# pcf.net
KiCad netlist of a schematic drawn in Altium Designer
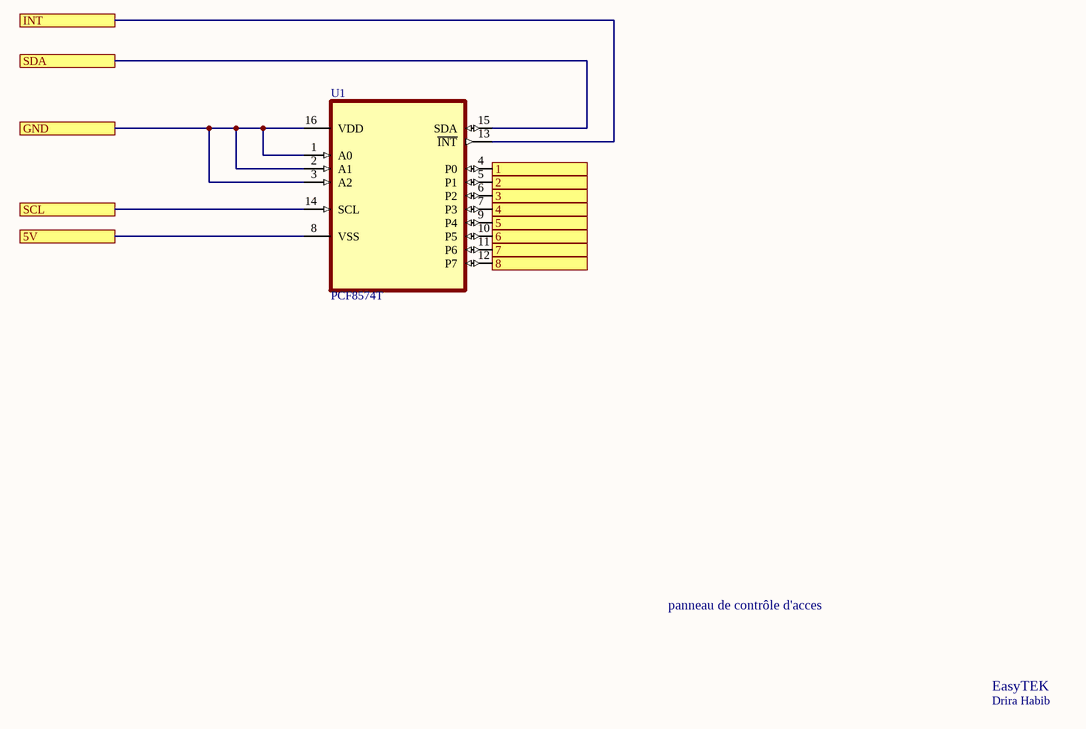
[diagram p0: pcf.SchDoc]

(export (version "E")
  (design (tool "Eeschema 10.0.6"))
  (components
    (comp (ref "U1")
      (value "PCF8574T")
      (footprint "SOIC127P1032X265-16N")
      (description "I/O Expander 8 IÂ²C 100 kHz 20-SSOP")
      (fields (field (name "MF") "NXP Semiconductors"))
      (libsource (lib "PCF8574T") (part "PCF8574T"))
    )
  )
  (nets
    (net (code "1") (name "/1") (class "Default")
      (node (ref "U1") (pin "4") (pinfunction "P0_4") (pintype "bidirectional"))
    )
    (net (code "2") (name "/2") (class "Default")
      (node (ref "U1") (pin "5") (pinfunction "P1_5") (pintype "bidirectional"))
    )
    (net (code "3") (name "/3") (class "Default")
      (node (ref "U1") (pin "6") (pinfunction "P2_6") (pintype "bidirectional"))
    )
    (net (code "4") (name "/4") (class "Default")
      (node (ref "U1") (pin "7") (pinfunction "P3_7") (pintype "bidirectional"))
    )
    (net (code "5") (name "/5") (class "Default")
      (node (ref "U1") (pin "9") (pinfunction "P4_9") (pintype "bidirectional"))
    )
    (net (code "6") (name "/5V") (class "Default")
      (node (ref "U1") (pin "8") (pinfunction "VSS_8") (pintype "passive"))
    )
    (net (code "7") (name "/6") (class "Default")
      (node (ref "U1") (pin "10") (pinfunction "P5_10") (pintype "bidirectional"))
    )
    (net (code "8") (name "/7") (class "Default")
      (node (ref "U1") (pin "11") (pinfunction "P6_11") (pintype "bidirectional"))
    )
    (net (code "9") (name "/8") (class "Default")
      (node (ref "U1") (pin "12") (pinfunction "P7_12") (pintype "bidirectional"))
    )
    (net (code "10") (name "/GND") (class "Default")
      (node (ref "U1") (pin "1") (pinfunction "A0_1") (pintype "input"))
      (node (ref "U1") (pin "16") (pinfunction "VDD_16") (pintype "power_in"))
      (node (ref "U1") (pin "2") (pinfunction "A1_2") (pintype "input"))
      (node (ref "U1") (pin "3") (pinfunction "A2_3") (pintype "input"))
    )
    (net (code "11") (name "/INT") (class "Default")
      (node (ref "U1") (pin "13") (pinfunction "~{INT}_13") (pintype "output"))
    )
    (net (code "12") (name "/SCL") (class "Default")
      (node (ref "U1") (pin "14") (pinfunction "SCL_14") (pintype "input"))
    )
    (net (code "13") (name "/SDA") (class "Default")
      (node (ref "U1") (pin "15") (pinfunction "SDA_15") (pintype "bidirectional"))
    )
  )
)
